# 4d_-_BSPD_Detection_Timer.net
KiCad netlist of a schematic drawn in Altium Designer
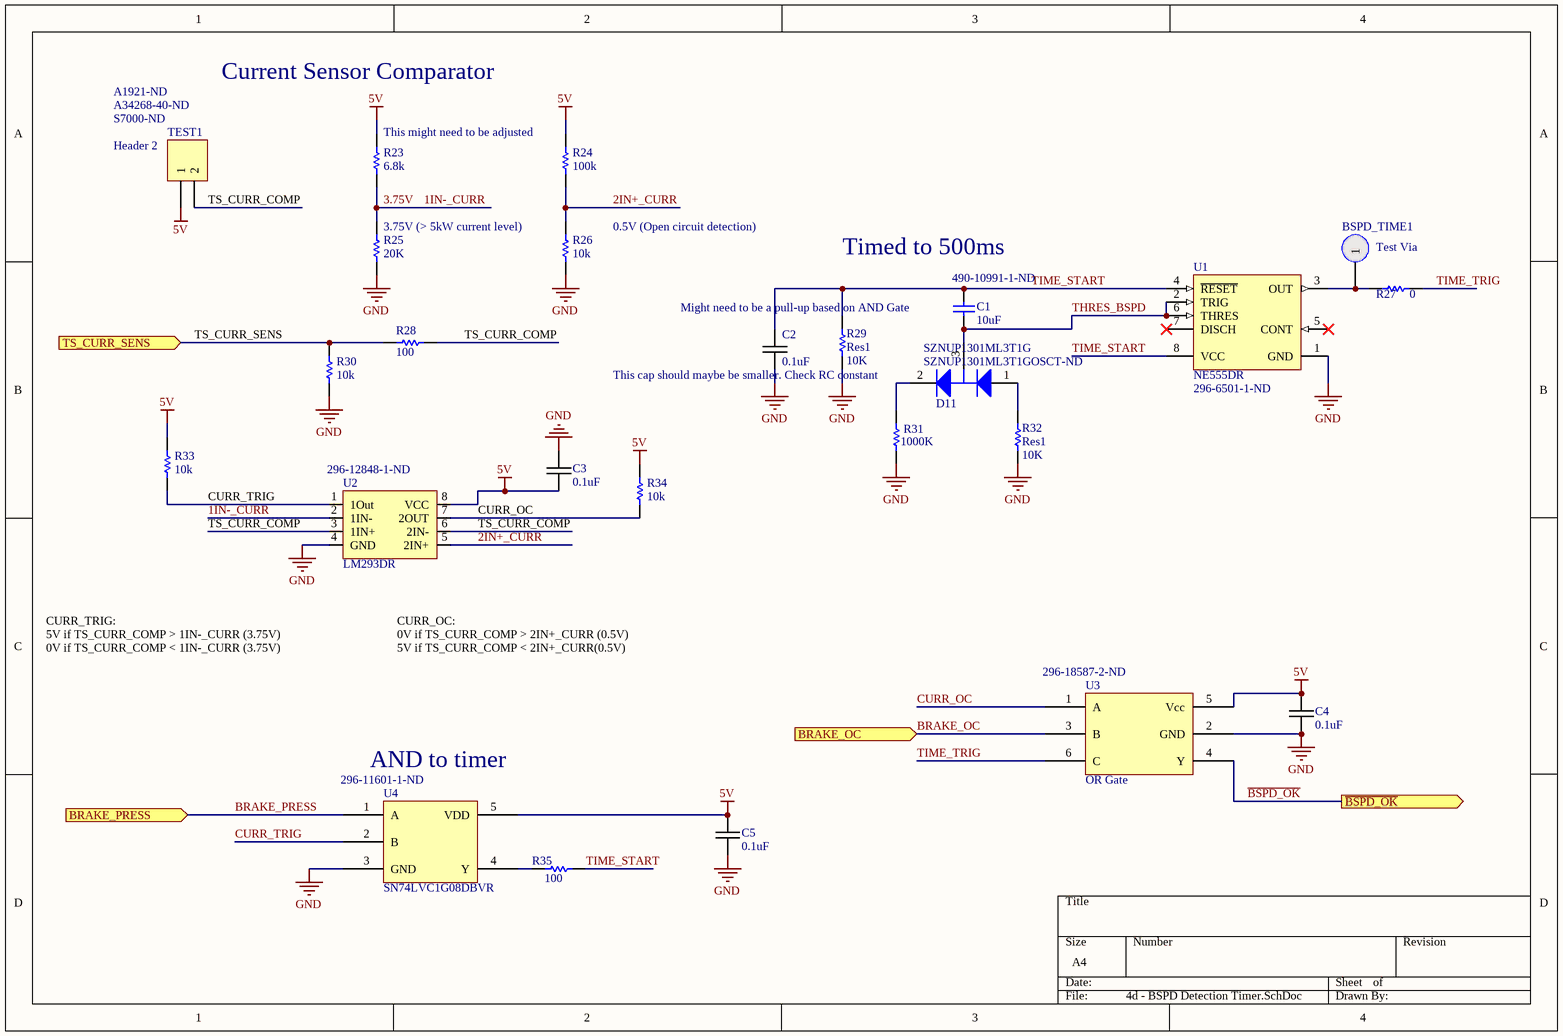
[diagram p0: 4d - BSPD Detection Timer.SchDoc]

(export (version "E")
  (design (tool "Eeschema 10.0.6"))
  (components
    (comp (ref "BSPD_TIME1")
      (value "Test Via")
      (footprint "Test Via")
      (libsource (lib "BRAKETEMPComponents") (part "Test VIa"))
    )
    (comp (ref "C1")
      (value "10uF")
      (footprint "1608[0603]")
      (description "Capacitor (Semiconductor SIM Model)")
      (fields
        (field (name "SUPPLIER PART NUMBER 1") "490-10991-1-ND")
        (field (name "Comment") "Cap Semi")
        (field (name "PUBLISHER") "Altium Limited")
      )
      (libsource (lib "Miscellaneous Devices") (part "Cap Semi"))
    )
    (comp (ref "C2")
      (value "0.1uF")
      (footprint "1608[0603]")
      (description "CAP CER 0.1UF 50V X7R 0603")
      (fields
        (field (name "MANUFACTURER") "Kemet")
        (field (name "MANUFACTURER PART NUMBER") "C0603C104K5RACAUTO")
      )
      (libsource (lib "vh_altium_library") (part "0805C-100nF-25V-X7R-MUR"))
    )
    (comp (ref "C3")
      (value "0.1uF")
      (footprint "1608[0603]")
      (description "CAP CER 0.1UF 50V X7R 0603")
      (fields
        (field (name "MANUFACTURER") "Kemet")
        (field (name "MANUFACTURER PART NUMBER") "C0603C104K5RACAUTO")
      )
      (libsource (lib "vh_altium_library") (part "0805C-100nF-25V-X7R-MUR"))
    )
    (comp (ref "C4")
      (value "0.1uF")
      (footprint "1608[0603]")
      (description "CAP CER 0.1UF 50V X7R 0603")
      (fields
        (field (name "MANUFACTURER") "Kemet")
        (field (name "MANUFACTURER PART NUMBER") "C0603C104K5RACAUTO")
      )
      (libsource (lib "vh_altium_library") (part "0805C-100nF-25V-X7R-MUR"))
    )
    (comp (ref "C5")
      (value "0.1uF")
      (footprint "1608[0603]")
      (description "CAP CER 0.1UF 50V X7R 0603")
      (fields
        (field (name "MANUFACTURER") "Kemet")
        (field (name "MANUFACTURER PART NUMBER") "C0603C104K5RACAUTO")
      )
      (libsource (lib "vh_altium_library") (part "0805C-100nF-25V-X7R-MUR"))
    )
    (comp (ref "D11")
      (value "SZNUP1301ML3T1G")
      (footprint "ONSC-SOT-23-3-318-08_V")
      (fields
        (field (name "MANUFACTURER") "On Semiconductor")
        (field (name "SUPPLIER PART NUMBER 1") "SZNUP1301ML3T1GOSCT-ND")
      )
      (libsource (lib "Altium Content Vault") (part "ONSC-NUP1301-SOT-23-3-318-08"))
    )
    (comp (ref "R23")
      (value "Volt. Div. R1")
      (footprint "1608[0603]")
      (description "RES SMD 6.8K OHM 5% 1/4W 0603")
      (fields
        (field (name "MANUFACTURER") "Rohm Semiconductor")
        (field (name "MANUFACTURER PART NUMBER") "ESR03EZPJ682")
        (field (name "RESISTANCE (OHMS)") "6.8k")
      )
      (libsource (lib "Miscellaneous Devices") (part "Res1"))
    )
    (comp (ref "R24")
      (value "Volt. Div. R1")
      (footprint "1608[0603]")
      (description "RES SMD 6.8K OHM 5% 1/4W 0603")
      (fields
        (field (name "MANUFACTURER") "Rohm Semiconductor")
        (field (name "MANUFACTURER PART NUMBER") "ESR03EZPJ682")
        (field (name "RESISTANCE (OHMS)") "100k")
      )
      (libsource (lib "Miscellaneous Devices") (part "Res1"))
    )
    (comp (ref "R25")
      (value "20K")
      (footprint "1608[0603]")
      (description "RES SMD 20K OHM 5% 1/4W 0603")
      (fields
        (field (name "MANUFACTURER") "Rohm Semiconductor")
        (field (name "MANUFACTURER PART NUMBER") "ESR03EZPJ203")
        (field (name "PUBLISHER") "Altium Limited")
      )
      (libsource (lib "Miscellaneous Devices") (part "Res1"))
    )
    (comp (ref "R26")
      (value "10k")
      (footprint "1608[0603]")
      (description "RES SMD 20K OHM 5% 1/4W 0603")
      (fields
        (field (name "MANUFACTURER") "Rohm Semiconductor")
        (field (name "MANUFACTURER PART NUMBER") "ESR03EZPJ203")
        (field (name "PUBLISHER") "Altium Limited")
      )
      (libsource (lib "Miscellaneous Devices") (part "Res1"))
    )
    (comp (ref "R27")
      (value "0")
      (footprint "1608[0603]")
      (description "RES SMD 0.0 OHM JUMPER 1/4W 0603")
      (fields
        (field (name "MANUFACTURER") "Vishay Dale")
        (field (name "MANUFACTURER PART NUMBER") "CRCW06030000Z0EAHP")
        (field (name "PUBLISHER") "Altium Limited")
      )
      (libsource (lib "Miscellaneous Devices") (part "Res1"))
    )
    (comp (ref "R28")
      (value "100")
      (footprint "1608[0603]")
      (description "RES SMD 20K OHM 5% 1/4W 0603")
      (fields
        (field (name "MANUFACTURER") "Rohm Semiconductor")
        (field (name "MANUFACTURER PART NUMBER") "ESR03EZPJ203")
        (field (name "PUBLISHER") "Altium Limited")
      )
      (libsource (lib "Miscellaneous Devices") (part "Res1"))
    )
    (comp (ref "R29")
      (value "Res1")
      (footprint "1608[0603]")
      (description "RES SMD 10K OHM 5% 1/4W 0603")
      (fields
        (field (name "ALTIUM_VALUE") "10K")
        (field (name "MANUFACTURER") "Rohm Semiconductor")
        (field (name "MANUFACTURER PART NUMBER") "ESR03EZPJ103")
        (field (name "PUBLISHER") "Altium Limited")
      )
      (libsource (lib "Miscellaneous Devices") (part "Res1"))
    )
    (comp (ref "R30")
      (value "10k")
      (footprint "1608[0603]")
      (description "RES SMD 20K OHM 5% 1/4W 0603")
      (fields
        (field (name "MANUFACTURER") "Rohm Semiconductor")
        (field (name "MANUFACTURER PART NUMBER") "ESR03EZPJ203")
        (field (name "PUBLISHER") "Altium Limited")
      )
      (libsource (lib "Miscellaneous Devices") (part "Res1"))
    )
    (comp (ref "R31")
      (value "1000K")
      (footprint "RESC0603(1608)_L")
      (description "0603 (1608 Metric) Chip Resistor")
      (libsource (lib "Altium Content Vault") (part "RES_3"))
    )
    (comp (ref "R32")
      (value "Res1")
      (footprint "1608[0603]")
      (description "RES SMD 10K OHM 5% 1/4W 0603")
      (fields
        (field (name "ALTIUM_VALUE") "10K")
        (field (name "MANUFACTURER") "Rohm Semiconductor")
        (field (name "MANUFACTURER PART NUMBER") "ESR03EZPJ103")
        (field (name "PUBLISHER") "Altium Limited")
      )
      (libsource (lib "Miscellaneous Devices") (part "Res1"))
    )
    (comp (ref "R33")
      (value "10k")
      (footprint "1608[0603]")
      (description "RES SMD 20K OHM 5% 1/4W 0603")
      (fields
        (field (name "MANUFACTURER") "Rohm Semiconductor")
        (field (name "MANUFACTURER PART NUMBER") "ESR03EZPJ203")
        (field (name "PUBLISHER") "Altium Limited")
      )
      (libsource (lib "Miscellaneous Devices") (part "Res1"))
    )
    (comp (ref "R34")
      (value "10k")
      (footprint "1608[0603]")
      (description "RES SMD 20K OHM 5% 1/4W 0603")
      (fields
        (field (name "MANUFACTURER") "Rohm Semiconductor")
        (field (name "MANUFACTURER PART NUMBER") "ESR03EZPJ203")
        (field (name "PUBLISHER") "Altium Limited")
      )
      (libsource (lib "Miscellaneous Devices") (part "Res1"))
    )
    (comp (ref "R35")
      (value "100")
      (footprint "1608[0603]")
      (description "RES SMD 20K OHM 5% 1/4W 0603")
      (fields
        (field (name "MANUFACTURER") "Rohm Semiconductor")
        (field (name "MANUFACTURER PART NUMBER") "ESR03EZPJ203")
        (field (name "PUBLISHER") "Altium Limited")
      )
      (libsource (lib "Miscellaneous Devices") (part "Res1"))
    )
    (comp (ref "TEST1")
      (value "Header 2")
      (footprint "2 Pin Connector")
      (description "Header, 2-Pin")
      (fields
        (field (name "MANUFACTURER") "Harwin Inc.")
        (field (name "MANUFACTURER PART NUMBER") "M20-9990246")
        (field (name "SUPPLIER PART NUMBER 1") "S7000-ND")
        (field (name "SUPPLIER PART NUMBER 2") "A34268-40-ND")
        (field (name "SUPPLIER PART NUMBER 3") "A1921-ND")
        (field (name "PUBLISHER") "Altium Limited")
      )
      (libsource (lib "Miscellaneous Connectors") (part "Header 2"))
    )
    (comp (ref "U1")
      (value "NE555DR")
      (footprint "D0008A_M")
      (fields (field (name "SUPPLIER PART NUMBER 1") "296-6501-1-ND"))
      (libsource (lib "Altium Content Vault") (part "CMP-1685-00007-1"))
    )
    (comp (ref "U2")
      (value "LM293DR")
      (footprint "LM293DR")
      (description "IC Dual Comparator")
      (fields (field (name "SUPPLIER PART NUMBER 1") "296-12848-1-ND"))
      (libsource (lib "ACB_lib") (part "LM293DR"))
    )
    (comp (ref "U3")
      (value "OR Gate")
      (footprint "SOT23-6_M")
      (fields (field (name "SUPPLIER PART NUMBER 1") "296-18587-2-ND"))
      (libsource (lib "Schlib1") (part "4-input OR Gate"))
    )
    (comp (ref "U4")
      (value "SN74LVC1G08DBVR")
      (footprint "SSOP5-P-0.95")
      (fields (field (name "SUPPLIER PART NUMBER 1") "296-11601-1-ND"))
      (libsource (lib "ACB_lib") (part "SN74LVC1G08DBVR"))
    )
  )
  (nets
    (net (code "1") (name "/1IN-_CURR") (class "Default")
      (node (ref "R23") (pin "1") (pinfunction "1_1") (pintype "passive"))
      (node (ref "R25") (pin "2") (pinfunction "2_2") (pintype "passive"))
      (node (ref "U2") (pin "2") (pinfunction "1IN-_2") (pintype "passive"))
    )
    (net (code "2") (name "/2IN+_CURR") (class "Default")
      (node (ref "R24") (pin "1") (pinfunction "1_1") (pintype "passive"))
      (node (ref "R26") (pin "2") (pinfunction "2_2") (pintype "passive"))
      (node (ref "U2") (pin "5") (pinfunction "2IN+_5") (pintype "passive"))
    )
    (net (code "3") (name "/BRAKE_OC") (class "Default")
      (node (ref "U3") (pin "3") (pinfunction "B_3") (pintype "passive"))
    )
    (net (code "4") (name "/BRAKE_PRESS") (class "Default")
      (node (ref "U4") (pin "1") (pinfunction "A_1") (pintype "passive"))
    )
    (net (code "5") (name "/CURR_OC") (class "Default")
      (node (ref "R34") (pin "1") (pinfunction "1_1") (pintype "passive"))
      (node (ref "U2") (pin "7") (pinfunction "2OUT_7") (pintype "passive"))
      (node (ref "U3") (pin "1") (pinfunction "A_1") (pintype "passive"))
    )
    (net (code "6") (name "/CURR_TRIG") (class "Default")
      (node (ref "R33") (pin "1") (pinfunction "1_1") (pintype "passive"))
      (node (ref "U2") (pin "1") (pinfunction "1Out_1") (pintype "passive"))
      (node (ref "U4") (pin "2") (pinfunction "B_2") (pintype "passive"))
    )
    (net (code "7") (name "/THRES_BSPD") (class "Default")
      (node (ref "C1") (pin "1") (pinfunction "1_1") (pintype "passive"))
      (node (ref "D11") (pin "3") (pinfunction "K/A_3") (pintype "passive"))
      (node (ref "U1") (pin "2") (pinfunction "TRIG_2") (pintype "input"))
      (node (ref "U1") (pin "6") (pinfunction "THRES_6") (pintype "input"))
    )
    (net (code "8") (name "/TIME_START") (class "Default")
      (node (ref "C1") (pin "2") (pinfunction "2_2") (pintype "passive"))
      (node (ref "C2") (pin "1") (pintype "passive"))
      (node (ref "R29") (pin "2") (pinfunction "2_2") (pintype "passive"))
      (node (ref "R35") (pin "1") (pinfunction "1_1") (pintype "passive"))
      (node (ref "U1") (pin "4") (pinfunction "~{RESET}_4") (pintype "input"))
      (node (ref "U1") (pin "8") (pinfunction "VCC_8") (pintype "power_in"))
    )
    (net (code "9") (name "/TIME_TRIG") (class "Default")
      (node (ref "R27") (pin "1") (pinfunction "1_1") (pintype "passive"))
      (node (ref "U3") (pin "6") (pinfunction "C_6") (pintype "passive"))
    )
    (net (code "10") (name "/TS_CURR_COMP") (class "Default")
      (node (ref "R28") (pin "1") (pinfunction "1_1") (pintype "passive"))
      (node (ref "TEST1") (pin "2") (pinfunction "2_2") (pintype "passive"))
      (node (ref "U2") (pin "3") (pinfunction "1IN+_3") (pintype "passive"))
      (node (ref "U2") (pin "6") (pinfunction "2IN-_6") (pintype "passive"))
    )
    (net (code "11") (name "/TS_CURR_SENS") (class "Default")
      (node (ref "R28") (pin "2") (pinfunction "2_2") (pintype "passive"))
      (node (ref "R30") (pin "2") (pinfunction "2_2") (pintype "passive"))
    )
    (net (code "12") (name "/~{BSPD_OK}") (class "Default")
      (node (ref "U3") (pin "4") (pinfunction "Y_4") (pintype "passive"))
    )
    (net (code "13") (name "5V") (class "Default")
      (node (ref "C3") (pin "1") (pintype "passive"))
      (node (ref "C4") (pin "1") (pintype "passive"))
      (node (ref "C5") (pin "1") (pintype "passive"))
      (node (ref "R23") (pin "2") (pinfunction "2_2") (pintype "passive"))
      (node (ref "R24") (pin "2") (pinfunction "2_2") (pintype "passive"))
      (node (ref "R33") (pin "2") (pinfunction "2_2") (pintype "passive"))
      (node (ref "R34") (pin "2") (pinfunction "2_2") (pintype "passive"))
      (node (ref "TEST1") (pin "1") (pinfunction "1_1") (pintype "passive"))
      (node (ref "U2") (pin "8") (pinfunction "VCC_8") (pintype "passive"))
      (node (ref "U3") (pin "5") (pinfunction "Vcc_5") (pintype "passive"))
      (node (ref "U4") (pin "5") (pinfunction "VDD_5") (pintype "passive"))
    )
    (net (code "14") (name "GND") (class "Default")
      (node (ref "C2") (pin "2") (pintype "passive"))
      (node (ref "C3") (pin "2") (pintype "passive"))
      (node (ref "C4") (pin "2") (pintype "passive"))
      (node (ref "C5") (pin "2") (pintype "passive"))
      (node (ref "R25") (pin "1") (pinfunction "1_1") (pintype "passive"))
      (node (ref "R26") (pin "1") (pinfunction "1_1") (pintype "passive"))
      (node (ref "R29") (pin "1") (pinfunction "1_1") (pintype "passive"))
      (node (ref "R30") (pin "1") (pinfunction "1_1") (pintype "passive"))
      (node (ref "R31") (pin "1") (pinfunction "1_1") (pintype "passive"))
      (node (ref "R32") (pin "1") (pinfunction "1_1") (pintype "passive"))
      (node (ref "U1") (pin "1") (pinfunction "GND_1") (pintype "power_in"))
      (node (ref "U2") (pin "4") (pinfunction "GND_4") (pintype "passive"))
      (node (ref "U3") (pin "2") (pinfunction "GND_2") (pintype "passive"))
      (node (ref "U4") (pin "3") (pinfunction "GND_3") (pintype "passive"))
    )
    (net (code "15") (name "Net-(D11-A)") (class "Default")
      (node (ref "D11") (pin "1") (pinfunction "A_1") (pintype "passive"))
      (node (ref "R32") (pin "2") (pinfunction "2_2") (pintype "passive"))
    )
    (net (code "16") (name "Net-(D11-K)") (class "Default")
      (node (ref "D11") (pin "2") (pinfunction "K_2") (pintype "passive"))
      (node (ref "R31") (pin "2") (pinfunction "2_2") (pintype "passive"))
    )
    (net (code "17") (name "Net-(U1-OUT)") (class "Default")
      (node (ref "BSPD_TIME1") (pin "1") (pinfunction "1_1") (pintype "passive"))
      (node (ref "R27") (pin "2") (pinfunction "2_2") (pintype "passive"))
      (node (ref "U1") (pin "3") (pinfunction "OUT_3") (pintype "output"))
    )
    (net (code "18") (name "Net-(U4-Y)") (class "Default")
      (node (ref "R35") (pin "2") (pinfunction "2_2") (pintype "passive"))
      (node (ref "U4") (pin "4") (pinfunction "Y_4") (pintype "passive"))
    )
    (net (code "19") (name "unconnected-(U1-CONT-Pad5)") (class "Default")
      (node (ref "U1") (pin "5") (pinfunction "CONT_5") (pintype "input+no_connect"))
    )
    (net (code "20") (name "unconnected-(U1-DISCH-Pad7)") (class "Default")
      (node (ref "U1") (pin "7") (pinfunction "DISCH_7") (pintype "open_collector+no_connect"))
    )
  )
)
